# Sheet3.net
KiCad netlist of a schematic drawn in Altium Designer
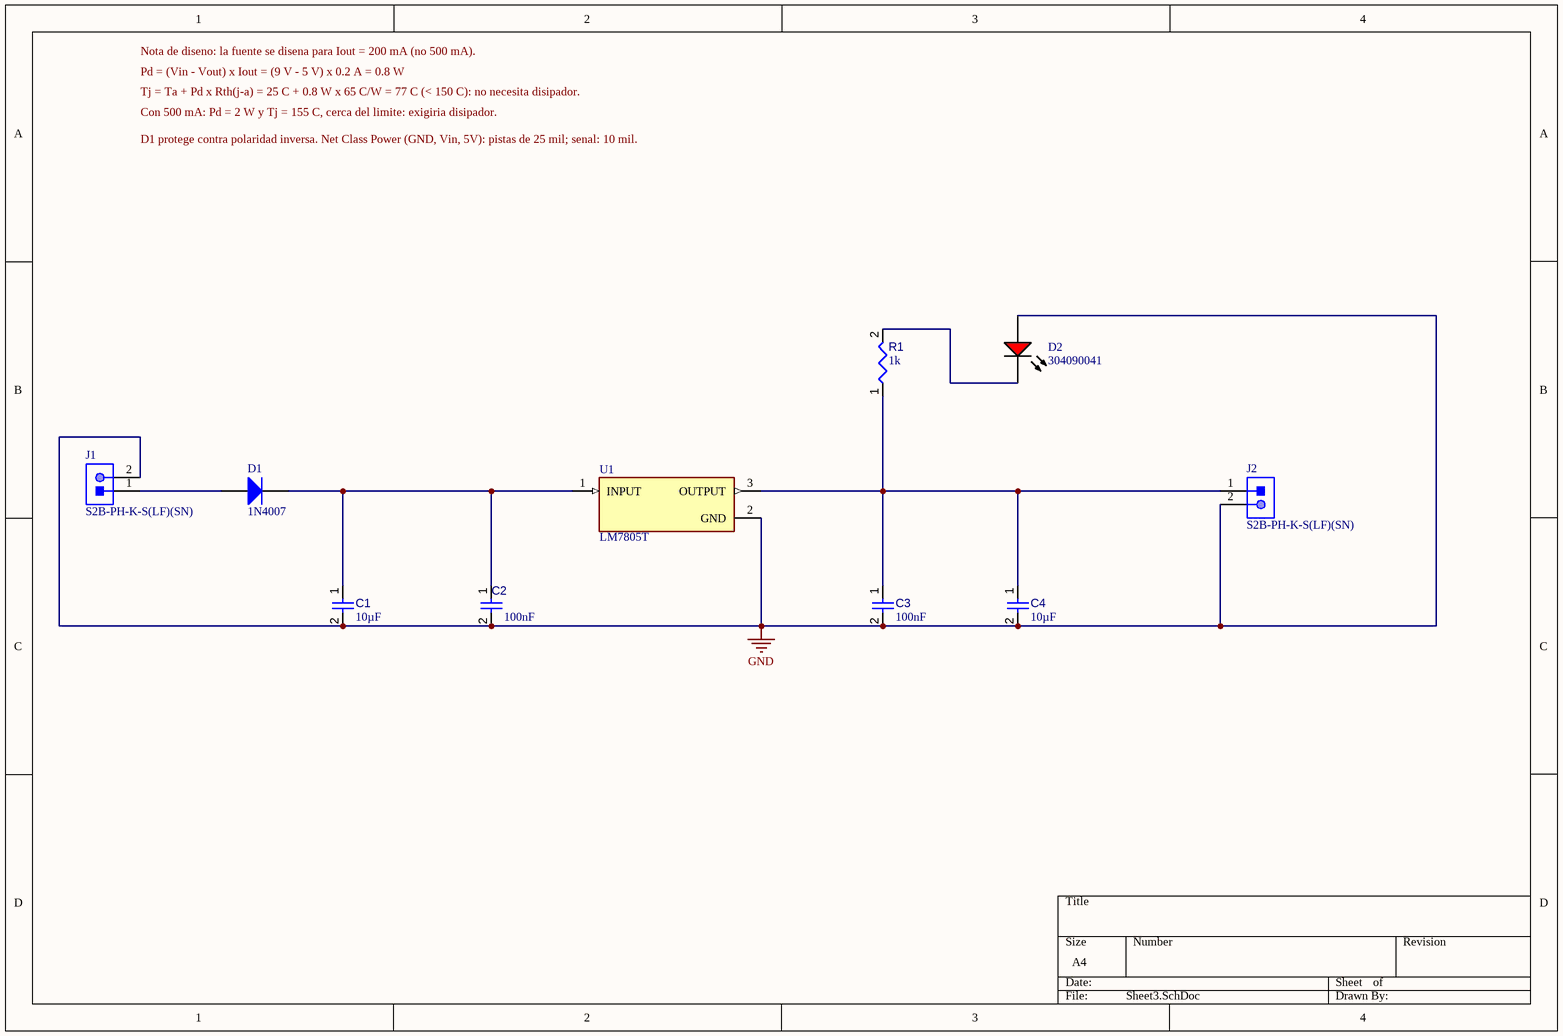
[diagram p0: Sheet3.SchDoc]

(export (version "E")
  (design (tool "Eeschema 10.0.6"))
  (components
    (comp (ref "C1")
      (value "10µF")
      (footprint "CAPC0805(2012)145_L")
      (description "Chip Capacitor, 10µF +/-20%, 25V, 0805, Thickness 1.45 mm")
      (fields (field (name "TOLERANCE") "10%") (field (name "Comment") "Capacitor 10µF +/-20% 25V 0805"))
      (libsource (lib "EFRAIN ALVARADO") (part "CAP-NP-2"))
    )
    (comp (ref "C2")
      (value "100nF")
      (footprint "CAPC0402(1005)60_L")
      (description "Chip Capacitor, 100nF +/-20%, 25V, 0402, Thickness 0.6 mm")
      (fields (field (name "TOLERANCE") "10%") (field (name "Comment") "Capacitor 100nF +/-20% 25V 0402"))
      (libsource (lib "EFRAIN ALVARADO") (part "CAP-NP-2"))
    )
    (comp (ref "C3")
      (value "100nF")
      (footprint "CAPC0402(1005)60_L")
      (description "Chip Capacitor, 100nF +/-20%, 25V, 0402, Thickness 0.6 mm")
      (fields (field (name "TOLERANCE") "10%") (field (name "Comment") "Capacitor 100nF +/-20% 25V 0402"))
      (libsource (lib "EFRAIN ALVARADO") (part "CAP-NP-2"))
    )
    (comp (ref "C4")
      (value "10µF")
      (footprint "CAPC0805(2012)145_L")
      (description "Chip Capacitor, 10µF +/-20%, 25V, 0805, Thickness 1.45 mm")
      (fields (field (name "TOLERANCE") "10%") (field (name "Comment") "Capacitor 10µF +/-20% 25V 0805"))
      (libsource (lib "EFRAIN ALVARADO") (part "CAP-NP-2"))
    )
    (comp (ref "D1")
      (value "1N4007")
      (footprint "FAIR-DO-41-2")
      (description "General Purpose Rectifier, 1.1 V, 1.0 A, -55 to 175 degC, 2-Pin DO-41, RoHS, Tape and Reel")
      (fields (field (name "MANUFACTURER") "Fairchild"))
      (libsource (lib "EFRAIN ALVARADO") (part "KESE-D_K1A2-2"))
    )
    (comp (ref "D2")
      (value "304090041")
      (footprint "LED-2P-2.28-3MM_A")
      (description "Red LED, 80 mW, 30 mA, -25 to 85 degC, 2-Pin THD")
      (fields (field (name "MANUFACTURER") "Shenzhen CGX"))
      (libsource (lib "EFRAIN ALVARADO") (part "LED-RED-AK-2"))
    )
    (comp (ref "J1")
      (value "S2B-PH-K-S(LF)(SN)")
      (footprint "JST-S2B-PH-K-S_V")
      (fields (field (name "MANUFACTURER") "Japan Solderless Terminals"))
      (libsource (lib "") (part "CN-1P-M-R2_1"))
    )
    (comp (ref "J2")
      (value "S2B-PH-K-S(LF)(SN)")
      (footprint "JST-S2B-PH-K-S_V")
      (fields (field (name "MANUFACTURER") "Japan Solderless Terminals"))
      (libsource (lib "EFRAIN ALVARADO") (part "CN-1P-M-R2"))
    )
    (comp (ref "R1")
      (value "1k")
      (footprint "RESC0402(1005)_L")
      (description "1K 0.063W 5% 0402 (1005 Metric)  SMD")
      (fields (field (name "POWER") "63mW") (field (name "TOLERANCE") "5%"))
      (libsource (lib "EFRAIN ALVARADO") (part "1KR2J"))
    )
    (comp (ref "U1")
      (value "LM7805T")
      (footprint "TO254P1011X457X1950-3")
      (description "3-Terminal 1.5A Positive Fixed Voltage Regulator")
      (fields (field (name "MF") "TAEJIN"))
      (libsource (lib "LM7805T") (part "LM7805T"))
    )
  )
  (nets
    (net (code "1") (name "GND") (class "Default")
      (node (ref "C1") (pin "2") (pinfunction "2_2") (pintype "passive"))
      (node (ref "C2") (pin "2") (pinfunction "2_2") (pintype "passive"))
      (node (ref "C3") (pin "2") (pinfunction "2_2") (pintype "passive"))
      (node (ref "C4") (pin "2") (pinfunction "2_2") (pintype "passive"))
      (node (ref "D2") (pin "1") (pinfunction "A_1") (pintype "passive"))
      (node (ref "J1") (pin "2") (pinfunction "2_2") (pintype "passive"))
      (node (ref "J2") (pin "2") (pinfunction "2_2") (pintype "passive"))
      (node (ref "U1") (pin "2") (pinfunction "GND_2") (pintype "power_in"))
    )
    (net (code "2") (name "Net-(D1-A)") (class "Default")
      (node (ref "D1") (pin "2") (pinfunction "A_2") (pintype "passive"))
      (node (ref "J1") (pin "1") (pinfunction "1_1") (pintype "passive"))
    )
    (net (code "3") (name "Net-(D1-K)") (class "Default")
      (node (ref "C1") (pin "1") (pinfunction "1_1") (pintype "passive"))
      (node (ref "C2") (pin "1") (pinfunction "1_1") (pintype "passive"))
      (node (ref "D1") (pin "1") (pinfunction "K_1") (pintype "passive"))
      (node (ref "U1") (pin "1") (pinfunction "INPUT_1") (pintype "input"))
    )
    (net (code "4") (name "Net-(D2-K)") (class "Default")
      (node (ref "D2") (pin "2") (pinfunction "K_2") (pintype "passive"))
      (node (ref "R1") (pin "2") (pinfunction "2_2") (pintype "passive"))
    )
    (net (code "5") (name "Net-(U1-OUTPUT)") (class "Default")
      (node (ref "C3") (pin "1") (pinfunction "1_1") (pintype "passive"))
      (node (ref "C4") (pin "1") (pinfunction "1_1") (pintype "passive"))
      (node (ref "J2") (pin "1") (pinfunction "1_1") (pintype "passive"))
      (node (ref "R1") (pin "1") (pinfunction "1_1") (pintype "passive"))
      (node (ref "U1") (pin "3") (pinfunction "OUTPUT_3") (pintype "output"))
    )
  )
)
